# pi433_r01.net
KiCad netlist of a schematic drawn in EAGLE
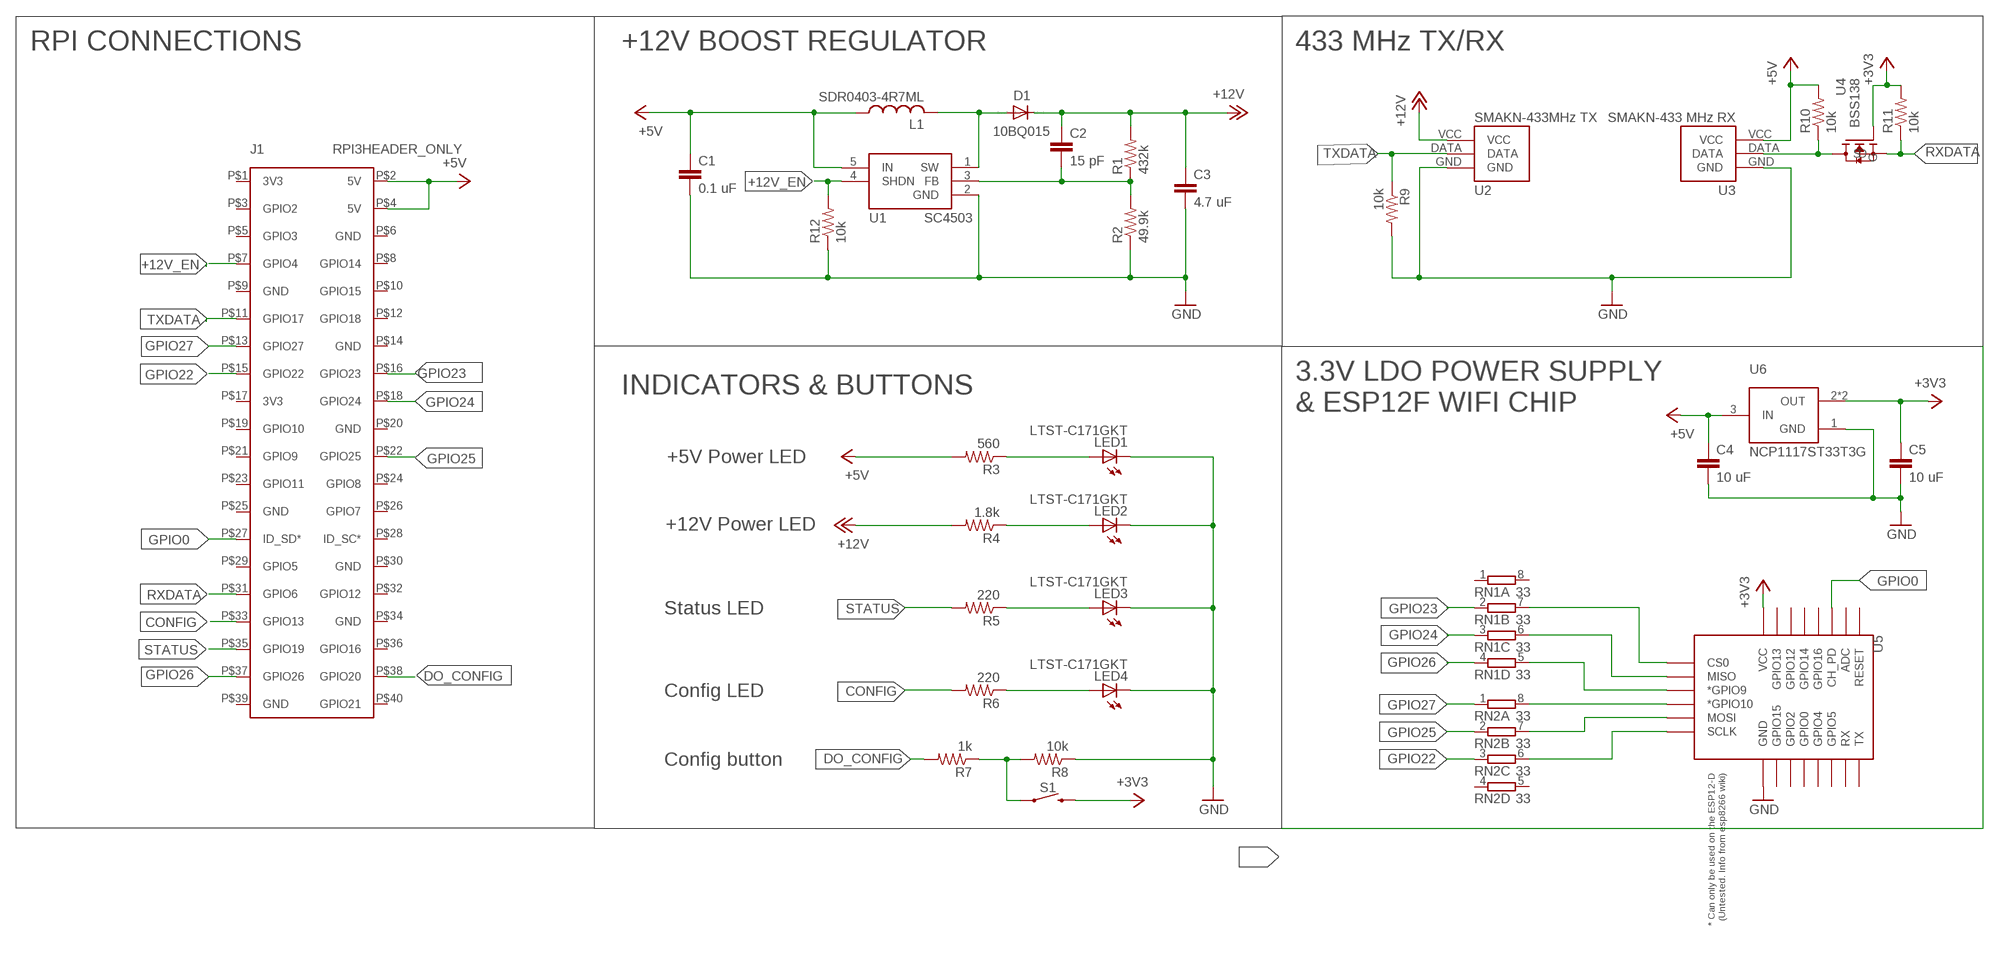
[diagram p0: schematic, sheet 1]

(export (version "E")
  (design (tool "Eeschema 10.0.6"))
  (components
    (comp (ref "C1")
      (value "0.1 uF")
      (footprint "eagle-import:C0603")
      (libsource (lib "eagle-import") (part "C-EUC0603"))
    )
    (comp (ref "C2")
      (value "15 pF")
      (footprint "eagle-import:C0603")
      (libsource (lib "eagle-import") (part "C-EUC0603"))
    )
    (comp (ref "C3")
      (value "4.7 uF")
      (footprint "eagle-import:C0805")
      (libsource (lib "eagle-import") (part "C-EUC0805"))
    )
    (comp (ref "C4")
      (value "10 uF")
      (footprint "eagle-import:C0805")
      (libsource (lib "eagle-import") (part "C-EUC0805"))
    )
    (comp (ref "C5")
      (value "10 uF")
      (footprint "eagle-import:C0805")
      (libsource (lib "eagle-import") (part "C-EUC0805"))
    )
    (comp (ref "D1")
      (value "10BQ015")
      (footprint "eagle-import:DO214AA")
      (libsource (lib "eagle-import") (part "DIODE-DO214AA"))
    )
    (comp (ref "J1")
      (value "RPI3HEADER_ONLY")
      (footprint "eagle-import:RPI3-HEADER_ONLY")
      (libsource (lib "eagle-import") (part "RPI3HEADER_ONLY"))
    )
    (comp (ref "L1")
      (value "SDR0403-4R7ML")
      (footprint "eagle-import:SDR0403")
      (libsource (lib "eagle-import") (part "SDR0403-4R7ML"))
    )
    (comp (ref "LED1")
      (value "LTST-C171GKT")
      (footprint "eagle-import:CHIPLED_0805")
      (libsource (lib "eagle-import") (part "LEDCHIPLED_0805"))
    )
    (comp (ref "LED2")
      (value "LTST-C171GKT")
      (footprint "eagle-import:CHIPLED_0805")
      (libsource (lib "eagle-import") (part "LEDCHIPLED_0805"))
    )
    (comp (ref "LED3")
      (value "LTST-C171GKT")
      (footprint "eagle-import:CHIPLED_0805")
      (libsource (lib "eagle-import") (part "LEDCHIPLED_0805"))
    )
    (comp (ref "LED4")
      (value "LTST-C171GKT")
      (footprint "eagle-import:CHIPLED_0805")
      (libsource (lib "eagle-import") (part "LEDCHIPLED_0805"))
    )
    (comp (ref "R1")
      (value "432k")
      (footprint "eagle-import:R0805")
      (libsource (lib "eagle-import") (part "R-US_R0805"))
    )
    (comp (ref "R2")
      (value "49.9k")
      (footprint "eagle-import:R0805")
      (libsource (lib "eagle-import") (part "R-US_R0805"))
    )
    (comp (ref "R3")
      (value "560")
      (footprint "eagle-import:R0805")
      (libsource (lib "eagle-import") (part "R-US_R0805"))
    )
    (comp (ref "R4")
      (value "1.8k")
      (footprint "eagle-import:R0805")
      (libsource (lib "eagle-import") (part "R-US_R0805"))
    )
    (comp (ref "R5")
      (value "220")
      (footprint "eagle-import:R0805")
      (libsource (lib "eagle-import") (part "R-US_R0805"))
    )
    (comp (ref "R6")
      (value "220")
      (footprint "eagle-import:R0805")
      (libsource (lib "eagle-import") (part "R-US_R0805"))
    )
    (comp (ref "R7")
      (value "1k")
      (footprint "eagle-import:R0805")
      (libsource (lib "eagle-import") (part "R-US_R0805"))
    )
    (comp (ref "R8")
      (value "10k")
      (footprint "eagle-import:R0805")
      (libsource (lib "eagle-import") (part "R-US_R0805"))
    )
    (comp (ref "R9")
      (value "10k")
      (footprint "eagle-import:R0805")
      (libsource (lib "eagle-import") (part "R-US_R0805"))
    )
    (comp (ref "R10")
      (value "10k")
      (footprint "eagle-import:R0805")
      (libsource (lib "eagle-import") (part "R-US_R0805"))
    )
    (comp (ref "R11")
      (value "10k")
      (footprint "eagle-import:R0805")
      (libsource (lib "eagle-import") (part "R-US_R0805"))
    )
    (comp (ref "R12")
      (value "10k")
      (footprint "eagle-import:R0805")
      (libsource (lib "eagle-import") (part "R-US_R0805"))
    )
    (comp (ref "RN1")
      (value "33")
      (footprint "eagle-import:CAY16")
      (libsource (lib "eagle-import") (part "4R-NCAY16"))
    )
    (comp (ref "RN2")
      (value "33")
      (footprint "eagle-import:CAY16")
      (libsource (lib "eagle-import") (part "4R-NCAY16"))
    )
    (comp (ref "S1")
      (value "MOMENTARY-SWITCH-SPST-SMD-6.0X3.5MM")
      (footprint "eagle-import:TACTILE_SWITCH_SMD_6.0X3.5MM")
      (libsource (lib "eagle-import") (part "MOMENTARY-SWITCH-SPST-SMD-6.0X3.5MM"))
    )
    (comp (ref "U1")
      (value "SC4503")
      (footprint "eagle-import:TSOT-23-5")
      (libsource (lib "eagle-import") (part "SC4503"))
    )
    (comp (ref "U2")
      (value "SMAKN-433TX")
      (footprint "eagle-import:SMAKN-433TX")
      (libsource (lib "eagle-import") (part "SMAKN-433TX"))
    )
    (comp (ref "U3")
      (value "SMAKN-433RX")
      (footprint "eagle-import:SMAKN-433RX")
      (libsource (lib "eagle-import") (part "SMAKN-433RX"))
    )
    (comp (ref "U4")
      (value "BSS138")
      (footprint "eagle-import:BSS138")
      (fields (field (name "MF") "Fairchild Semiconductor"))
      (libsource (lib "eagle-import") (part "BSS138"))
    )
    (comp (ref "U5")
      (value "ESP12ESMD")
      (footprint "eagle-import:ESP12E-SMD")
      (libsource (lib "eagle-import") (part "ESP12ESMD"))
    )
    (comp (ref "U6")
      (value "NCP1117ST33T3G")
      (footprint "eagle-import:SOT230P700X180-4N")
      (fields (field (name "MF") "ON Semiconductor"))
      (libsource (lib "eagle-import") (part "NCP1117ST33T3G"))
    )
  )
  (nets
    (net (code "1") (name "+3V3") (class "Default")
      (node (ref "C5") (pin "1") (pinfunction "1_1") (pintype "passive"))
      (node (ref "R11") (pin "2") (pinfunction "2_2") (pintype "passive"))
      (node (ref "S1") (pin "2") (pinfunction "2_2") (pintype "passive"))
      (node (ref "U4") (pin "G") (pinfunction "G_G") (pintype "passive"))
      (node (ref "U5") (pin "VCC") (pinfunction "VCC_VCC") (pintype "bidirectional"))
      (node (ref "U6") (pin "2") (pinfunction "OUT_2") (pintype "output"))
      (node (ref "U6") (pin "4") (pinfunction "OUT_4") (pintype "output"))
    )
    (net (code "2") (name "+5V") (class "Default")
      (node (ref "C1") (pin "1") (pinfunction "1_1") (pintype "passive"))
      (node (ref "C4") (pin "1") (pinfunction "1_1") (pintype "passive"))
      (node (ref "J1") (pin "P$2") (pinfunction "5V_P$2") (pintype "bidirectional"))
      (node (ref "J1") (pin "P$4") (pinfunction "5V_P$4") (pintype "bidirectional"))
      (node (ref "L1") (pin "P$1") (pinfunction "1_P$1") (pintype "passive"))
      (node (ref "R10") (pin "2") (pinfunction "2_2") (pintype "passive"))
      (node (ref "R3") (pin "2") (pinfunction "2_2") (pintype "passive"))
      (node (ref "U1") (pin "5") (pinfunction "IN_5") (pintype "power_in"))
      (node (ref "U3") (pin "VCC") (pinfunction "VCC_VCC") (pintype "bidirectional"))
      (node (ref "U6") (pin "3") (pinfunction "IN_3") (pintype "input"))
    )
    (net (code "3") (name "+12V") (class "Default")
      (node (ref "C2") (pin "1") (pinfunction "1_1") (pintype "passive"))
      (node (ref "C3") (pin "1") (pinfunction "1_1") (pintype "passive"))
      (node (ref "D1") (pin "C") (pinfunction "C_C") (pintype "passive"))
      (node (ref "R1") (pin "2") (pinfunction "2_2") (pintype "passive"))
      (node (ref "R4") (pin "2") (pinfunction "2_2") (pintype "passive"))
      (node (ref "U2") (pin "VCC") (pinfunction "VCC_VCC") (pintype "bidirectional"))
    )
    (net (code "4") (name "/+12V_EN") (class "Default")
      (node (ref "J1") (pin "P$7") (pinfunction "GPIO4_P$7") (pintype "bidirectional"))
      (node (ref "R12") (pin "2") (pinfunction "2_2") (pintype "passive"))
      (node (ref "U1") (pin "4") (pinfunction "SHDN_4") (pintype "input"))
    )
    (net (code "5") (name "/CONFIG") (class "Default")
      (node (ref "J1") (pin "P$33") (pinfunction "GPIO13_P$33") (pintype "bidirectional"))
      (node (ref "R6") (pin "2") (pinfunction "2_2") (pintype "passive"))
    )
    (net (code "6") (name "/DO_CONFIG") (class "Default")
      (node (ref "J1") (pin "P$38") (pinfunction "GPIO20_P$38") (pintype "bidirectional"))
      (node (ref "R7") (pin "2") (pinfunction "2_2") (pintype "passive"))
    )
    (net (code "7") (name "/GPIO0") (class "Default")
      (node (ref "J1") (pin "P$27") (pinfunction "ID_SD*_P$27") (pintype "bidirectional"))
      (node (ref "U5") (pin "CH_PD") (pinfunction "CH_PD_CH_PD") (pintype "bidirectional"))
    )
    (net (code "8") (name "/GPIO22") (class "Default")
      (node (ref "J1") (pin "P$15") (pinfunction "GPIO22_P$15") (pintype "bidirectional"))
      (node (ref "RN2") (pin "3") (pinfunction "1_3") (pintype "passive"))
    )
    (net (code "9") (name "/GPIO23") (class "Default")
      (node (ref "J1") (pin "P$16") (pinfunction "GPIO23_P$16") (pintype "bidirectional"))
      (node (ref "RN1") (pin "2") (pinfunction "1_2") (pintype "passive"))
    )
    (net (code "10") (name "/GPIO24") (class "Default")
      (node (ref "J1") (pin "P$18") (pinfunction "GPIO24_P$18") (pintype "bidirectional"))
      (node (ref "RN1") (pin "3") (pinfunction "1_3") (pintype "passive"))
    )
    (net (code "11") (name "/GPIO25") (class "Default")
      (node (ref "J1") (pin "P$22") (pinfunction "GPIO25_P$22") (pintype "bidirectional"))
      (node (ref "RN2") (pin "2") (pinfunction "1_2") (pintype "passive"))
    )
    (net (code "12") (name "/GPIO26") (class "Default")
      (node (ref "J1") (pin "P$37") (pinfunction "GPIO26_P$37") (pintype "bidirectional"))
      (node (ref "RN1") (pin "4") (pinfunction "1_4") (pintype "passive"))
    )
    (net (code "13") (name "/GPIO27") (class "Default")
      (node (ref "J1") (pin "P$13") (pinfunction "GPIO27_P$13") (pintype "bidirectional"))
      (node (ref "RN2") (pin "1") (pinfunction "1_1") (pintype "passive"))
    )
    (net (code "14") (name "/RXDATA") (class "Default")
      (node (ref "J1") (pin "P$31") (pinfunction "GPIO6_P$31") (pintype "bidirectional"))
      (node (ref "R11") (pin "1") (pinfunction "1_1") (pintype "passive"))
      (node (ref "U4") (pin "S") (pinfunction "S_S") (pintype "passive"))
    )
    (net (code "15") (name "/STATUS") (class "Default")
      (node (ref "J1") (pin "P$35") (pinfunction "GPIO19_P$35") (pintype "bidirectional"))
      (node (ref "R5") (pin "2") (pinfunction "2_2") (pintype "passive"))
    )
    (net (code "16") (name "/TXDATA") (class "Default")
      (node (ref "J1") (pin "P$11") (pinfunction "GPIO17_P$11") (pintype "bidirectional"))
      (node (ref "R9") (pin "1") (pinfunction "1_1") (pintype "passive"))
      (node (ref "U2") (pin "DATA") (pinfunction "DATA_DATA") (pintype "bidirectional"))
    )
    (net (code "17") (name "GND") (class "Default")
      (node (ref "C1") (pin "2") (pinfunction "2_2") (pintype "passive"))
      (node (ref "C3") (pin "2") (pinfunction "2_2") (pintype "passive"))
      (node (ref "C4") (pin "2") (pinfunction "2_2") (pintype "passive"))
      (node (ref "C5") (pin "2") (pinfunction "2_2") (pintype "passive"))
      (node (ref "LED1") (pin "C") (pinfunction "C_C") (pintype "passive"))
      (node (ref "LED2") (pin "C") (pinfunction "C_C") (pintype "passive"))
      (node (ref "LED3") (pin "C") (pinfunction "C_C") (pintype "passive"))
      (node (ref "LED4") (pin "C") (pinfunction "C_C") (pintype "passive"))
      (node (ref "R12") (pin "1") (pinfunction "1_1") (pintype "passive"))
      (node (ref "R2") (pin "1") (pinfunction "1_1") (pintype "passive"))
      (node (ref "R8") (pin "1") (pinfunction "1_1") (pintype "passive"))
      (node (ref "R9") (pin "2") (pinfunction "2_2") (pintype "passive"))
      (node (ref "U1") (pin "2") (pinfunction "GND_2") (pintype "input"))
      (node (ref "U2") (pin "GND") (pinfunction "GND_GND") (pintype "bidirectional"))
      (node (ref "U3") (pin "GND") (pinfunction "GND_GND") (pintype "bidirectional"))
      (node (ref "U5") (pin "GND") (pinfunction "GND_GND") (pintype "bidirectional"))
      (node (ref "U6") (pin "1") (pinfunction "GND_1") (pintype "power_in"))
    )
    (net (code "18") (name "Net-(L1-2)") (class "Default")
      (node (ref "D1") (pin "A") (pinfunction "A_A") (pintype "passive"))
      (node (ref "L1") (pin "P$2") (pinfunction "2_P$2") (pintype "passive"))
      (node (ref "U1") (pin "1") (pinfunction "SW_1") (pintype "input"))
    )
    (net (code "19") (name "Net-(LED1-PadA)") (class "Default")
      (node (ref "LED1") (pin "A") (pinfunction "A_A") (pintype "passive"))
      (node (ref "R3") (pin "1") (pinfunction "1_1") (pintype "passive"))
    )
    (net (code "20") (name "Net-(LED2-PadA)") (class "Default")
      (node (ref "LED2") (pin "A") (pinfunction "A_A") (pintype "passive"))
      (node (ref "R4") (pin "1") (pinfunction "1_1") (pintype "passive"))
    )
    (net (code "21") (name "Net-(LED3-PadA)") (class "Default")
      (node (ref "LED3") (pin "A") (pinfunction "A_A") (pintype "passive"))
      (node (ref "R5") (pin "1") (pinfunction "1_1") (pintype "passive"))
    )
    (net (code "22") (name "Net-(LED4-PadA)") (class "Default")
      (node (ref "LED4") (pin "A") (pinfunction "A_A") (pintype "passive"))
      (node (ref "R6") (pin "1") (pinfunction "1_1") (pintype "passive"))
    )
    (net (code "23") (name "Net-(R7-Pad1)") (class "Default")
      (node (ref "R7") (pin "1") (pinfunction "1_1") (pintype "passive"))
      (node (ref "R8") (pin "2") (pinfunction "2_2") (pintype "passive"))
      (node (ref "S1") (pin "1") (pinfunction "1_1") (pintype "passive"))
    )
    (net (code "24") (name "Net-(R10-Pad1)") (class "Default")
      (node (ref "R10") (pin "1") (pinfunction "1_1") (pintype "passive"))
      (node (ref "U3") (pin "DATA") (pinfunction "DATA_DATA") (pintype "bidirectional"))
      (node (ref "U4") (pin "D") (pinfunction "D_D") (pintype "passive"))
    )
    (net (code "25") (name "Net-(RN1B-2)") (class "Default")
      (node (ref "RN1") (pin "7") (pinfunction "2_7") (pintype "passive"))
      (node (ref "U5") (pin "CS0") (pinfunction "CS0_CS0") (pintype "bidirectional"))
    )
    (net (code "26") (name "Net-(RN1C-2)") (class "Default")
      (node (ref "RN1") (pin "6") (pinfunction "2_6") (pintype "passive"))
      (node (ref "U5") (pin "MISO") (pinfunction "MISO_MISO") (pintype "bidirectional"))
    )
    (net (code "27") (name "Net-(RN1D-2)") (class "Default")
      (node (ref "RN1") (pin "5") (pinfunction "2_5") (pintype "passive"))
      (node (ref "U5") (pin "GPIO9") (pinfunction "*GPIO9_GPIO9") (pintype "bidirectional"))
    )
    (net (code "28") (name "Net-(RN2A-2)") (class "Default")
      (node (ref "RN2") (pin "8") (pinfunction "2_8") (pintype "passive"))
      (node (ref "U5") (pin "GPIO10") (pinfunction "*GPIO10_GPIO10") (pintype "bidirectional"))
    )
    (net (code "29") (name "Net-(RN2B-2)") (class "Default")
      (node (ref "RN2") (pin "7") (pinfunction "2_7") (pintype "passive"))
      (node (ref "U5") (pin "MOSI") (pinfunction "MOSI_MOSI") (pintype "bidirectional"))
    )
    (net (code "30") (name "Net-(RN2C-2)") (class "Default")
      (node (ref "RN2") (pin "6") (pinfunction "2_6") (pintype "passive"))
      (node (ref "U5") (pin "SCLK") (pinfunction "SCLK_SCLK") (pintype "bidirectional"))
    )
    (net (code "31") (name "Net-(U1-FB)") (class "Default")
      (node (ref "C2") (pin "2") (pinfunction "2_2") (pintype "passive"))
      (node (ref "R1") (pin "1") (pinfunction "1_1") (pintype "passive"))
      (node (ref "R2") (pin "2") (pinfunction "2_2") (pintype "passive"))
      (node (ref "U1") (pin "3") (pinfunction "FB_3") (pintype "input"))
    )
    (net (code "32") (name "unconnected-(J1-3V3-PadP$1)") (class "Default")
      (node (ref "J1") (pin "P$1") (pinfunction "3V3_P$1") (pintype "bidirectional"))
    )
    (net (code "33") (name "unconnected-(J1-3V3-PadP$17)") (class "Default")
      (node (ref "J1") (pin "P$17") (pinfunction "3V3_P$17") (pintype "bidirectional"))
    )
    (net (code "34") (name "unconnected-(J1-GND-PadP$6)") (class "Default")
      (node (ref "J1") (pin "P$6") (pinfunction "GND_P$6") (pintype "bidirectional"))
    )
    (net (code "35") (name "unconnected-(J1-GND-PadP$9)") (class "Default")
      (node (ref "J1") (pin "P$9") (pinfunction "GND_P$9") (pintype "bidirectional"))
    )
    (net (code "36") (name "unconnected-(J1-GND-PadP$14)") (class "Default")
      (node (ref "J1") (pin "P$14") (pinfunction "GND_P$14") (pintype "bidirectional"))
    )
    (net (code "37") (name "unconnected-(J1-GND-PadP$20)") (class "Default")
      (node (ref "J1") (pin "P$20") (pinfunction "GND_P$20") (pintype "bidirectional"))
    )
    (net (code "38") (name "unconnected-(J1-GND-PadP$25)") (class "Default")
      (node (ref "J1") (pin "P$25") (pinfunction "GND_P$25") (pintype "bidirectional"))
    )
    (net (code "39") (name "unconnected-(J1-GND-PadP$30)") (class "Default")
      (node (ref "J1") (pin "P$30") (pinfunction "GND_P$30") (pintype "bidirectional"))
    )
    (net (code "40") (name "unconnected-(J1-GND-PadP$34)") (class "Default")
      (node (ref "J1") (pin "P$34") (pinfunction "GND_P$34") (pintype "bidirectional"))
    )
    (net (code "41") (name "unconnected-(J1-GND-PadP$39)") (class "Default")
      (node (ref "J1") (pin "P$39") (pinfunction "GND_P$39") (pintype "bidirectional"))
    )
    (net (code "42") (name "unconnected-(J1-GPIO2-PadP$3)") (class "Default")
      (node (ref "J1") (pin "P$3") (pinfunction "GPIO2_P$3") (pintype "bidirectional"))
    )
    (net (code "43") (name "unconnected-(J1-GPIO3-PadP$5)") (class "Default")
      (node (ref "J1") (pin "P$5") (pinfunction "GPIO3_P$5") (pintype "bidirectional"))
    )
    (net (code "44") (name "unconnected-(J1-GPIO5-PadP$29)") (class "Default")
      (node (ref "J1") (pin "P$29") (pinfunction "GPIO5_P$29") (pintype "bidirectional"))
    )
    (net (code "45") (name "unconnected-(J1-GPIO7-PadP$26)") (class "Default")
      (node (ref "J1") (pin "P$26") (pinfunction "GPIO7_P$26") (pintype "bidirectional"))
    )
    (net (code "46") (name "unconnected-(J1-GPIO8-PadP$24)") (class "Default")
      (node (ref "J1") (pin "P$24") (pinfunction "GPIO8_P$24") (pintype "bidirectional"))
    )
    (net (code "47") (name "unconnected-(J1-GPIO9-PadP$21)") (class "Default")
      (node (ref "J1") (pin "P$21") (pinfunction "GPIO9_P$21") (pintype "bidirectional"))
    )
    (net (code "48") (name "unconnected-(J1-GPIO10-PadP$19)") (class "Default")
      (node (ref "J1") (pin "P$19") (pinfunction "GPIO10_P$19") (pintype "bidirectional"))
    )
    (net (code "49") (name "unconnected-(J1-GPIO11-PadP$23)") (class "Default")
      (node (ref "J1") (pin "P$23") (pinfunction "GPIO11_P$23") (pintype "bidirectional"))
    )
    (net (code "50") (name "unconnected-(J1-GPIO12-PadP$32)") (class "Default")
      (node (ref "J1") (pin "P$32") (pinfunction "GPIO12_P$32") (pintype "bidirectional"))
    )
    (net (code "51") (name "unconnected-(J1-GPIO14-PadP$8)") (class "Default")
      (node (ref "J1") (pin "P$8") (pinfunction "GPIO14_P$8") (pintype "bidirectional"))
    )
    (net (code "52") (name "unconnected-(J1-GPIO15-PadP$10)") (class "Default")
      (node (ref "J1") (pin "P$10") (pinfunction "GPIO15_P$10") (pintype "bidirectional"))
    )
    (net (code "53") (name "unconnected-(J1-GPIO16-PadP$36)") (class "Default")
      (node (ref "J1") (pin "P$36") (pinfunction "GPIO16_P$36") (pintype "bidirectional"))
    )
    (net (code "54") (name "unconnected-(J1-GPIO18-PadP$12)") (class "Default")
      (node (ref "J1") (pin "P$12") (pinfunction "GPIO18_P$12") (pintype "bidirectional"))
    )
    (net (code "55") (name "unconnected-(J1-GPIO21-PadP$40)") (class "Default")
      (node (ref "J1") (pin "P$40") (pinfunction "GPIO21_P$40") (pintype "bidirectional"))
    )
    (net (code "56") (name "unconnected-(J1-ID_SC*-PadP$28)") (class "Default")
      (node (ref "J1") (pin "P$28") (pinfunction "ID_SC*_P$28") (pintype "bidirectional"))
    )
    (net (code "57") (name "unconnected-(RN1-Pad1)") (class "Default")
      (node (ref "RN1") (pin "1") (pinfunction "1_1") (pintype "passive"))
    )
    (net (code "58") (name "unconnected-(RN1A-2-Pad8)") (class "Default")
      (node (ref "RN1") (pin "8") (pinfunction "2_8") (pintype "passive"))
    )
    (net (code "59") (name "unconnected-(RN2D-1-Pad4)") (class "Default")
      (node (ref "RN2") (pin "4") (pinfunction "1_4") (pintype "passive"))
    )
    (net (code "60") (name "unconnected-(RN2D-2-Pad5)") (class "Default")
      (node (ref "RN2") (pin "5") (pinfunction "2_5") (pintype "passive"))
    )
    (net (code "61") (name "unconnected-(U5-PadADC)") (class "Default")
      (node (ref "U5") (pin "ADC") (pinfunction "ADC_ADC") (pintype "bidirectional"))
    )
    (net (code "62") (name "unconnected-(U5-PadGPIO0)") (class "Default")
      (node (ref "U5") (pin "GPIO0") (pinfunction "GPIO0_GPIO0") (pintype "bidirectional"))
    )
    (net (code "63") (name "unconnected-(U5-PadGPIO2)") (class "Default")
      (node (ref "U5") (pin "GPIO2") (pinfunction "GPIO2_GPIO2") (pintype "bidirectional"))
    )
    (net (code "64") (name "unconnected-(U5-PadGPIO4)") (class "Default")
      (node (ref "U5") (pin "GPIO4") (pinfunction "GPIO4_GPIO4") (pintype "bidirectional"))
    )
    (net (code "65") (name "unconnected-(U5-PadGPIO5)") (class "Default")
      (node (ref "U5") (pin "GPIO5") (pinfunction "GPIO5_GPIO5") (pintype "bidirectional"))
    )
    (net (code "66") (name "unconnected-(U5-PadGPIO12)") (class "Default")
      (node (ref "U5") (pin "GPIO12") (pinfunction "GPIO12_GPIO12") (pintype "bidirectional"))
    )
    (net (code "67") (name "unconnected-(U5-PadGPIO13)") (class "Default")
      (node (ref "U5") (pin "GPIO13") (pinfunction "GPIO13_GPIO13") (pintype "bidirectional"))
    )
    (net (code "68") (name "unconnected-(U5-PadGPIO14)") (class "Default")
      (node (ref "U5") (pin "GPIO14") (pinfunction "GPIO14_GPIO14") (pintype "bidirectional"))
    )
    (net (code "69") (name "unconnected-(U5-PadGPIO15)") (class "Default")
      (node (ref "U5") (pin "GPIO15") (pinfunction "GPIO15_GPIO15") (pintype "bidirectional"))
    )
    (net (code "70") (name "unconnected-(U5-PadGPIO16)") (class "Default")
      (node (ref "U5") (pin "GPIO16") (pinfunction "GPIO16_GPIO16") (pintype "bidirectional"))
    )
    (net (code "71") (name "unconnected-(U5-PadRESET)") (class "Default")
      (node (ref "U5") (pin "RESET") (pinfunction "RESET_RESET") (pintype "bidirectional"))
    )
    (net (code "72") (name "unconnected-(U5-RX-PadRXD0)") (class "Default")
      (node (ref "U5") (pin "RXD0") (pinfunction "RX_RXD0") (pintype "bidirectional"))
    )
    (net (code "73") (name "unconnected-(U5-TX-PadTXD0)") (class "Default")
      (node (ref "U5") (pin "TXD0") (pinfunction "TX_TXD0") (pintype "bidirectional"))
    )
  )
)
